# SCH_Better_Heating_Plate_2022-11-13.net
KiCad netlist of a schematic drawn in EasyEDA
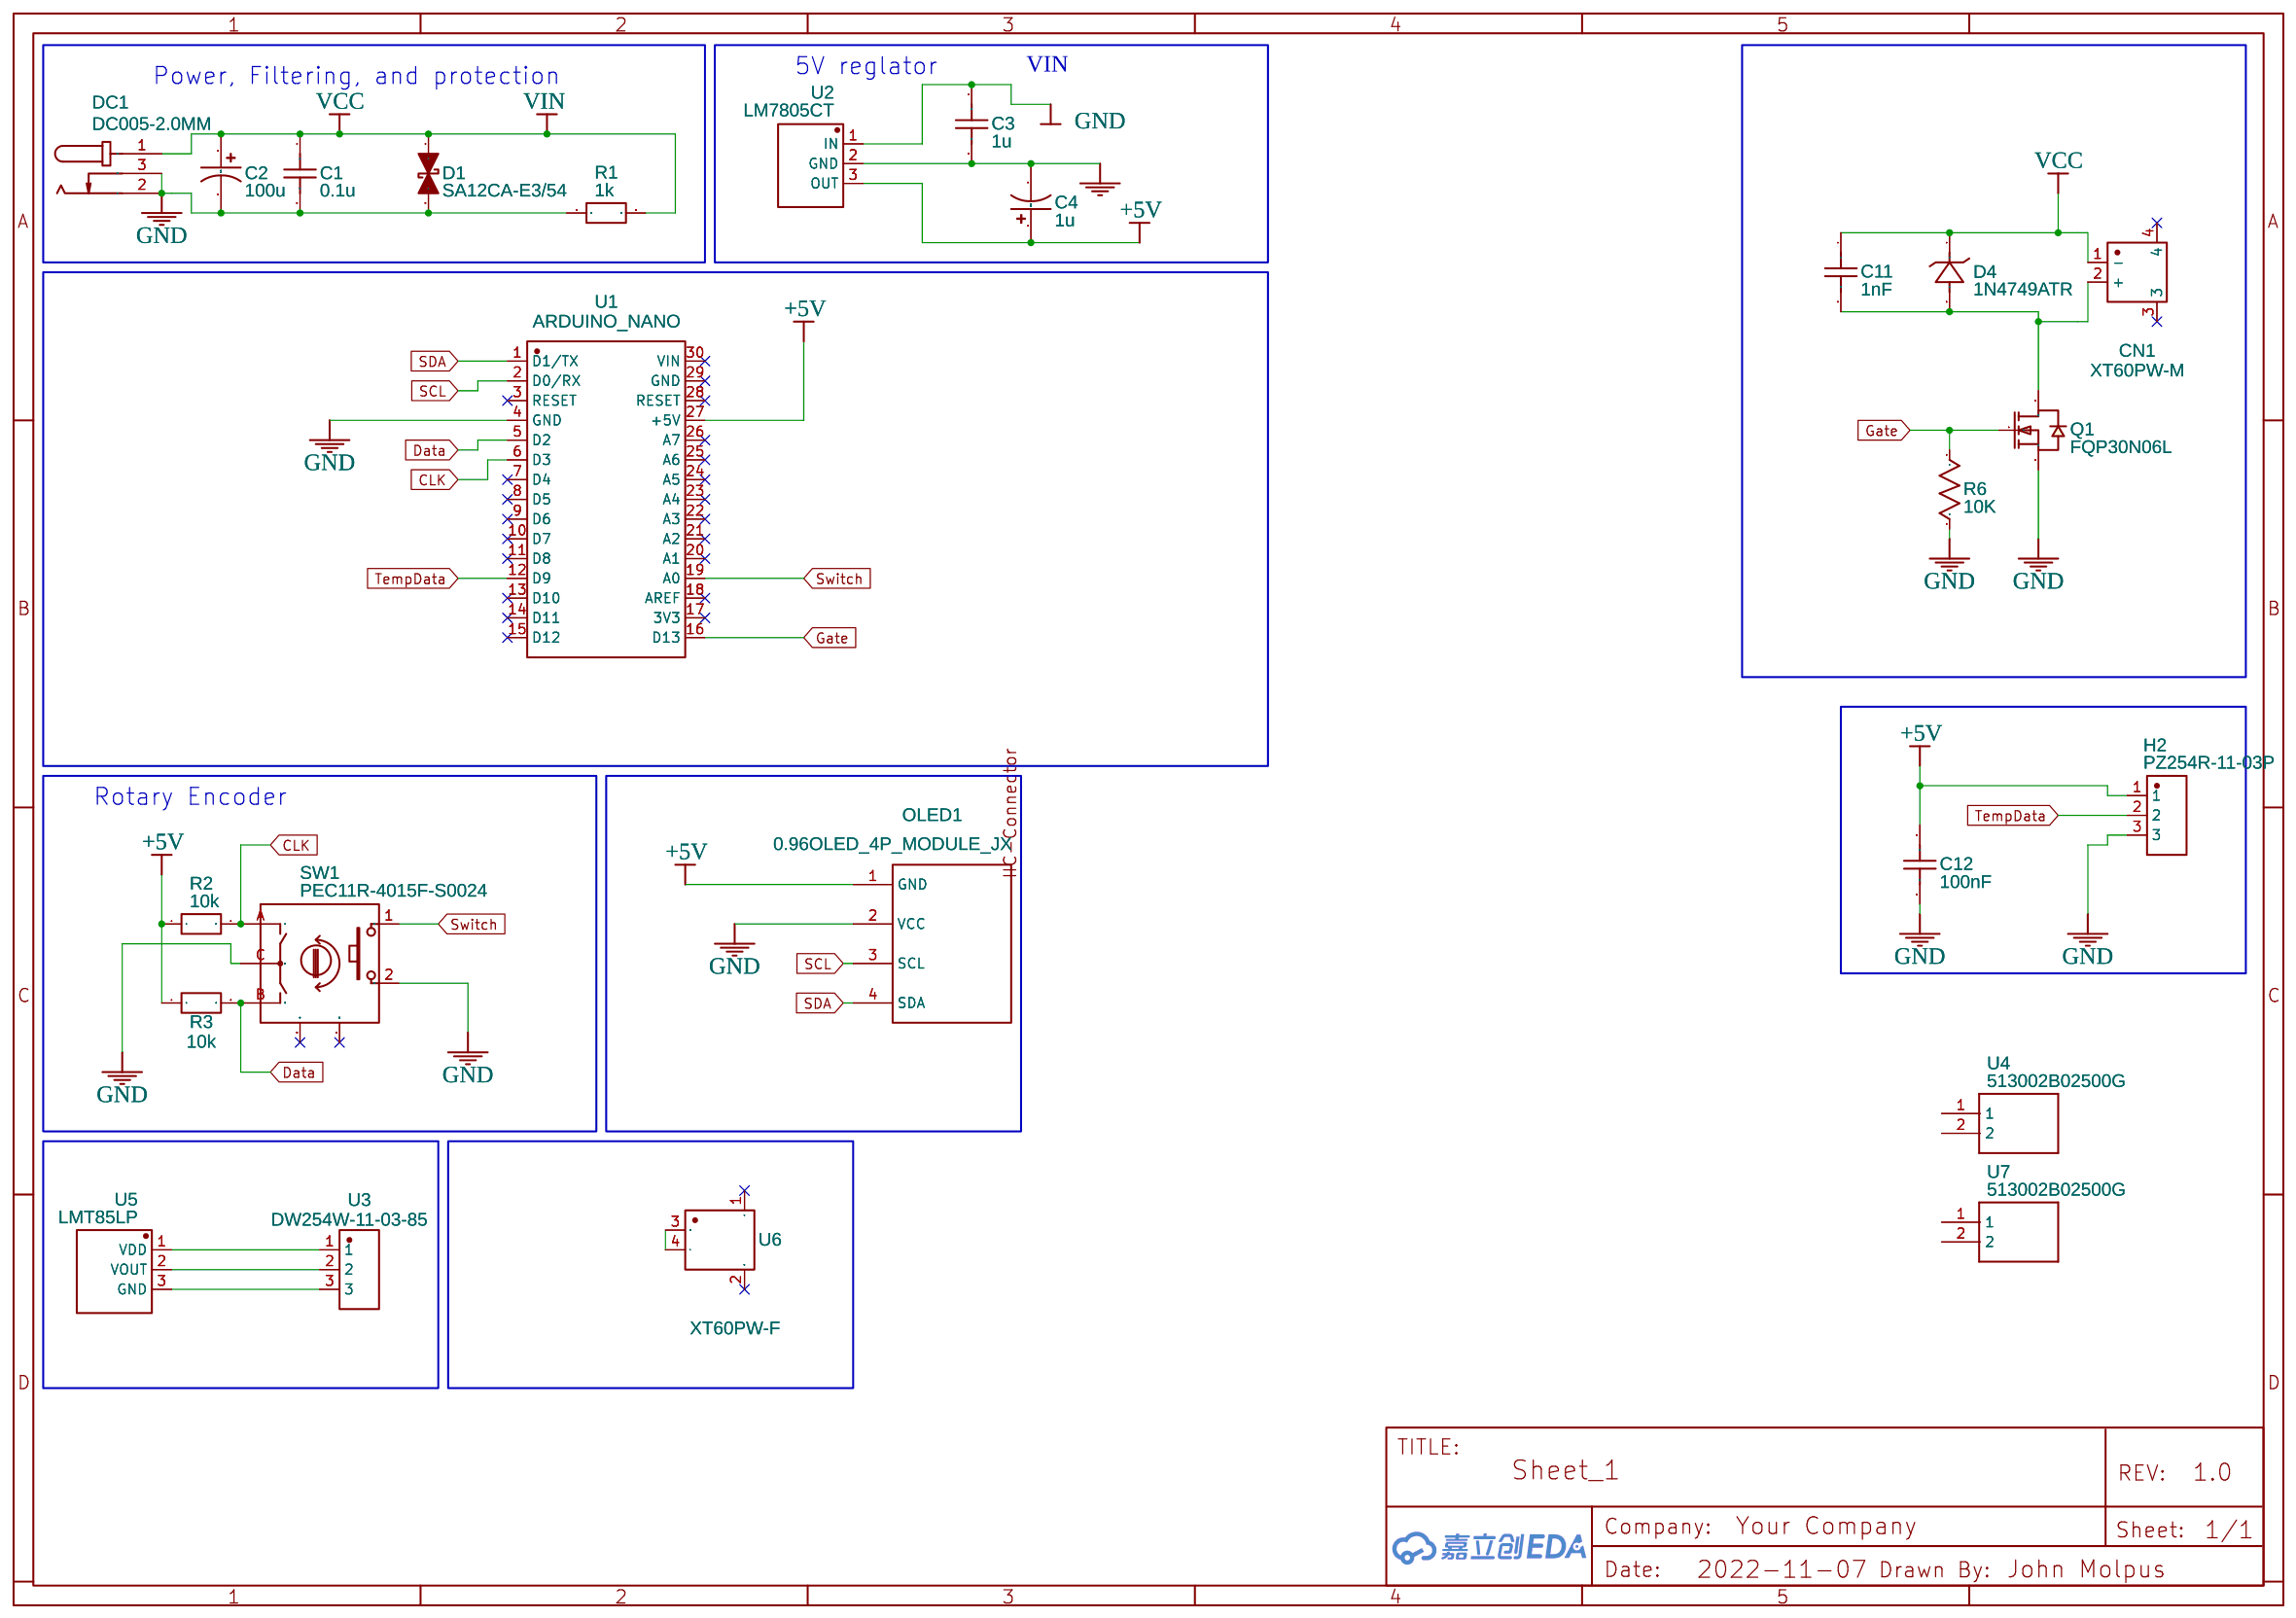
[diagram p0: schematic sheet]

(export (version "E")
  (design (tool "Eeschema 10.0.6"))
  (components
    (comp (ref "C1") (value "0.1u") (libsource (lib "") (part "C_RAD-0.2_US")))
    (comp (ref "C2") (value "100u") (libsource (lib "") (part "CE_TH_D3.0×F1.5_US_1")))
    (comp (ref "C3") (value "1u") (libsource (lib "") (part "C_RAD-0.1_US")))
    (comp (ref "C4") (value "1u") (libsource (lib "") (part "CE_TH_D3.0×F1.5_US")))
    (comp (ref "C11") (value "1nF") (libsource (lib "") (part "C_RAD-0.1_US")))
    (comp (ref "C12") (value "100nF") (libsource (lib "") (part "C_RAD-0.1_US")))
    (comp (ref "CN1")
      (value "XT60PW-M")
      (fields (field (name "BOM_Supplier Part") "C98732"))
      (libsource (lib "") (part "XT60PW-M"))
    )
    (comp (ref "D1")
      (value "SA12CA-E3/54")
      (fields (field (name "BOM_Supplier Part") "C1975517"))
      (libsource (lib "") (part "SA12CA-E3/54"))
    )
    (comp (ref "D4")
      (value "1N4749ATR")
      (fields (field (name "BOM_Supplier Part") "C890088"))
      (libsource (lib "") (part "1N4749ATR"))
    )
    (comp (ref "DC1")
      (value "DC005-2.0MM")
      (fields (field (name "BOM_Supplier Part") "C111567"))
      (libsource (lib "") (part "DC005-2.0MM"))
    )
    (comp (ref "H2")
      (value "PZ254R-11-03P")
      (fields (field (name "BOM_Supplier Part") "C492411"))
      (libsource (lib "") (part "PZ254R-11-03P"))
    )
    (comp (ref "OLED1")
      (value "0.96OLED_4P_MODULE_JX")
      (fields (field (name "BOM_Supplier Part") "C9900004566"))
      (libsource (lib "") (part "0.96OLED_4P_MODULE_JX"))
    )
    (comp (ref "Q1")
      (value "FQP30N06L")
      (fields
        (field (name "BOM_Manufacturer Part") "FQP30N06L-VB")
        (field (name "BOM_Supplier Part") "C878826")
      )
      (libsource (lib "") (part "FQP30N06L"))
    )
    (comp (ref "R1") (value "1k") (libsource (lib "") (part "R_AXIAL-0.3_EU")))
    (comp (ref "R2") (value "10k") (libsource (lib "") (part "R_AXIAL-0.3_EU")))
    (comp (ref "R3") (value "10k") (libsource (lib "") (part "R_AXIAL-0.3_EU")))
    (comp (ref "R6") (value "10K") (libsource (lib "") (part "R_AXIAL-0.3_US")))
    (comp (ref "SW1")
      (value "PEC11R-4015F-S0024")
      (fields (field (name "BOM_Supplier Part") "C143789"))
      (libsource (lib "") (part "PEC11R-4015F-S0024"))
    )
    (comp (ref "U1")
      (value "ARDUINO_NANO")
      (fields (field (name "BOM_Supplier Part") "C9900017879"))
      (libsource (lib "") (part "ARDUINO_NANO"))
    )
    (comp (ref "U2")
      (value "LM7805CT")
      (fields (field (name "BOM_Supplier Part") "C22146"))
      (libsource (lib "") (part "LM7805CT"))
    )
    (comp (ref "U3")
      (value "DW254W-11-03-85")
      (fields (field (name "BOM_Supplier Part") "C2935993"))
      (libsource (lib "") (part "DW254W-11-03-85"))
    )
    (comp (ref "U4") (value "513002B02500G") (libsource (lib "") (part "513002B02500G")))
    (comp (ref "U5")
      (value "LMT85LP")
      (fields (field (name "BOM_Supplier Part") "C75856"))
      (libsource (lib "") (part "LMT85LP"))
    )
    (comp (ref "U6")
      (value "XT60PW-F")
      (fields
        (field (name "BOM_Manufacturer Part") "XT60PW-F 母头 板插卧式")
        (field (name "BOM_Supplier Part") "C9900000737")
      )
      (libsource (lib "") (part "XT60PW-F"))
    )
    (comp (ref "U7") (value "513002B02500G") (libsource (lib "") (part "513002B02500G")))
  )
  (nets
    (net (code "1") (name "+5V") (class "Default")
      (node (ref "C12") (pin "1") (pinfunction "1_1") (pintype "unspecified"))
      (node (ref "C4") (pin "1") (pinfunction "1_1") (pintype "unspecified"))
      (node (ref "H2") (pin "1") (pinfunction "1_1") (pintype "unspecified"))
      (node (ref "OLED1") (pin "1") (pinfunction "GND_1") (pintype "unspecified"))
      (node (ref "R2") (pin "1") (pinfunction "1_1") (pintype "unspecified"))
      (node (ref "R3") (pin "1") (pinfunction "1_1") (pintype "unspecified"))
      (node (ref "U1") (pin "27") (pinfunction "+5V_27") (pintype "unspecified"))
      (node (ref "U2") (pin "3") (pinfunction "OUT_3") (pintype "unspecified"))
    )
    (net (code "2") (name "CLK") (class "Default")
      (node (ref "R2") (pin "2") (pinfunction "2_2") (pintype "unspecified"))
      (node (ref "SW1") (pin "A") (pinfunction "A_A") (pintype "unspecified"))
      (node (ref "U1") (pin "6") (pinfunction "D3_6") (pintype "unspecified"))
    )
    (net (code "3") (name "Data") (class "Default")
      (node (ref "R3") (pin "2") (pinfunction "2_2") (pintype "unspecified"))
      (node (ref "SW1") (pin "B") (pinfunction "B_B") (pintype "unspecified"))
      (node (ref "U1") (pin "5") (pinfunction "D2_5") (pintype "unspecified"))
    )
    (net (code "4") (name "GND") (class "Default")
      (node (ref "C1") (pin "2") (pinfunction "2_2") (pintype "unspecified"))
      (node (ref "C12") (pin "2") (pinfunction "2_2") (pintype "unspecified"))
      (node (ref "C2") (pin "2") (pinfunction "2_2") (pintype "unspecified"))
      (node (ref "C3") (pin "2") (pinfunction "2_2") (pintype "unspecified"))
      (node (ref "C4") (pin "2") (pinfunction "2_2") (pintype "unspecified"))
      (node (ref "D1") (pin "2") (pinfunction "A_2") (pintype "input"))
      (node (ref "DC1") (pin "2") (pinfunction "2_2") (pintype "unspecified"))
      (node (ref "DC1") (pin "3") (pinfunction "3_3") (pintype "unspecified"))
      (node (ref "H2") (pin "3") (pinfunction "3_3") (pintype "unspecified"))
      (node (ref "OLED1") (pin "2") (pinfunction "VCC_2") (pintype "unspecified"))
      (node (ref "Q1") (pin "3") (pinfunction "S_3") (pintype "unspecified"))
      (node (ref "R1") (pin "1") (pinfunction "1_1") (pintype "unspecified"))
      (node (ref "R6") (pin "2") (pinfunction "2_2") (pintype "unspecified"))
      (node (ref "SW1") (pin "2") (pinfunction "2_2") (pintype "unspecified"))
      (node (ref "SW1") (pin "C") (pinfunction "C_C") (pintype "unspecified"))
      (node (ref "U1") (pin "4") (pinfunction "GND_4") (pintype "unspecified"))
      (node (ref "U2") (pin "2") (pinfunction "GND_2") (pintype "unspecified"))
    )
    (net (code "5") (name "Gate") (class "Default")
      (node (ref "Q1") (pin "1") (pinfunction "G_1") (pintype "unspecified"))
      (node (ref "R6") (pin "1") (pinfunction "1_1") (pintype "unspecified"))
      (node (ref "U1") (pin "16") (pinfunction "D13_16") (pintype "unspecified"))
    )
    (net (code "6") (name "Net-(CN1-+)") (class "Default")
      (node (ref "C11") (pin "2") (pinfunction "2_2") (pintype "unspecified"))
      (node (ref "CN1") (pin "2") (pinfunction "+_2") (pintype "unspecified"))
      (node (ref "D4") (pin "2") (pinfunction "A_2") (pintype "unspecified"))
      (node (ref "Q1") (pin "2") (pinfunction "D_2") (pintype "unspecified"))
    )
    (net (code "7") (name "Net-(U5-GND)") (class "Default")
      (node (ref "U3") (pin "3") (pinfunction "3_3") (pintype "unspecified"))
      (node (ref "U5") (pin "3") (pinfunction "GND_3") (pintype "unspecified"))
    )
    (net (code "8") (name "Net-(U5-VDD)") (class "Default")
      (node (ref "U3") (pin "1") (pinfunction "1_1") (pintype "unspecified"))
      (node (ref "U5") (pin "1") (pinfunction "VDD_1") (pintype "unspecified"))
    )
    (net (code "9") (name "Net-(U5-VOUT)") (class "Default")
      (node (ref "U3") (pin "2") (pinfunction "2_2") (pintype "unspecified"))
      (node (ref "U5") (pin "2") (pinfunction "VOUT_2") (pintype "unspecified"))
    )
    (net (code "10") (name "Net-(U6-Pad3)") (class "Default")
      (node (ref "U6") (pin "3") (pinfunction "3_3") (pintype "unspecified"))
      (node (ref "U6") (pin "4") (pinfunction "4_4") (pintype "unspecified"))
    )
    (net (code "11") (name "SCL") (class "Default")
      (node (ref "OLED1") (pin "3") (pinfunction "SCL_3") (pintype "unspecified"))
      (node (ref "U1") (pin "2") (pinfunction "D0/RX_2") (pintype "unspecified"))
    )
    (net (code "12") (name "SDA") (class "Default")
      (node (ref "OLED1") (pin "4") (pinfunction "SDA_4") (pintype "unspecified"))
      (node (ref "U1") (pin "1") (pinfunction "D1/TX_1") (pintype "unspecified"))
    )
    (net (code "13") (name "Switch") (class "Default")
      (node (ref "SW1") (pin "1") (pinfunction "1_1") (pintype "unspecified"))
      (node (ref "U1") (pin "19") (pinfunction "A0_19") (pintype "unspecified"))
    )
    (net (code "14") (name "TempData") (class "Default")
      (node (ref "H2") (pin "2") (pinfunction "2_2") (pintype "unspecified"))
      (node (ref "U1") (pin "12") (pinfunction "D9_12") (pintype "unspecified"))
    )
    (net (code "15") (name "VCC") (class "Default")
      (node (ref "C1") (pin "1") (pinfunction "1_1") (pintype "unspecified"))
      (node (ref "C11") (pin "1") (pinfunction "1_1") (pintype "unspecified"))
      (node (ref "C2") (pin "1") (pinfunction "1_1") (pintype "unspecified"))
      (node (ref "C3") (pin "1") (pinfunction "1_1") (pintype "unspecified"))
      (node (ref "CN1") (pin "1") (pinfunction "-_1") (pintype "unspecified"))
      (node (ref "D1") (pin "1") (pinfunction "K_1") (pintype "input"))
      (node (ref "D4") (pin "1") (pinfunction "C_1") (pintype "unspecified"))
      (node (ref "DC1") (pin "1") (pinfunction "1_1") (pintype "unspecified"))
      (node (ref "R1") (pin "2") (pinfunction "2_2") (pintype "unspecified"))
      (node (ref "U2") (pin "1") (pinfunction "IN_1") (pintype "unspecified"))
    )
    (net (code "16") (name "unconnected-(CN1-Pad3)") (class "Default")
      (node (ref "CN1") (pin "3") (pinfunction "3_3") (pintype "unspecified+no_connect"))
    )
    (net (code "17") (name "unconnected-(CN1-Pad4)") (class "Default")
      (node (ref "CN1") (pin "4") (pinfunction "4_4") (pintype "unspecified+no_connect"))
    )
    (net (code "18") (name "unconnected-(SW1-PadMT1)") (class "Default")
      (node (ref "SW1") (pin "MT1") (pinfunction "MT1_MT1") (pintype "unspecified+no_connect"))
    )
    (net (code "19") (name "unconnected-(SW1-PadMT2)") (class "Default")
      (node (ref "SW1") (pin "MT2") (pinfunction "MT2_MT2") (pintype "unspecified+no_connect"))
    )
    (net (code "20") (name "unconnected-(U1-3V3-Pad17)") (class "Default")
      (node (ref "U1") (pin "17") (pinfunction "3V3_17") (pintype "unspecified+no_connect"))
    )
    (net (code "21") (name "unconnected-(U1-A1-Pad20)") (class "Default")
      (node (ref "U1") (pin "20") (pinfunction "A1_20") (pintype "unspecified+no_connect"))
    )
    (net (code "22") (name "unconnected-(U1-A2-Pad21)") (class "Default")
      (node (ref "U1") (pin "21") (pinfunction "A2_21") (pintype "unspecified+no_connect"))
    )
    (net (code "23") (name "unconnected-(U1-A3-Pad22)") (class "Default")
      (node (ref "U1") (pin "22") (pinfunction "A3_22") (pintype "unspecified+no_connect"))
    )
    (net (code "24") (name "unconnected-(U1-A4-Pad23)") (class "Default")
      (node (ref "U1") (pin "23") (pinfunction "A4_23") (pintype "unspecified+no_connect"))
    )
    (net (code "25") (name "unconnected-(U1-A5-Pad24)") (class "Default")
      (node (ref "U1") (pin "24") (pinfunction "A5_24") (pintype "unspecified+no_connect"))
    )
    (net (code "26") (name "unconnected-(U1-A6-Pad25)") (class "Default")
      (node (ref "U1") (pin "25") (pinfunction "A6_25") (pintype "unspecified+no_connect"))
    )
    (net (code "27") (name "unconnected-(U1-A7-Pad26)") (class "Default")
      (node (ref "U1") (pin "26") (pinfunction "A7_26") (pintype "unspecified+no_connect"))
    )
    (net (code "28") (name "unconnected-(U1-AREF-Pad18)") (class "Default")
      (node (ref "U1") (pin "18") (pinfunction "AREF_18") (pintype "unspecified+no_connect"))
    )
    (net (code "29") (name "unconnected-(U1-D4-Pad7)") (class "Default")
      (node (ref "U1") (pin "7") (pinfunction "D4_7") (pintype "unspecified+no_connect"))
    )
    (net (code "30") (name "unconnected-(U1-D5-Pad8)") (class "Default")
      (node (ref "U1") (pin "8") (pinfunction "D5_8") (pintype "unspecified+no_connect"))
    )
    (net (code "31") (name "unconnected-(U1-D6-Pad9)") (class "Default")
      (node (ref "U1") (pin "9") (pinfunction "D6_9") (pintype "unspecified+no_connect"))
    )
    (net (code "32") (name "unconnected-(U1-D7-Pad10)") (class "Default")
      (node (ref "U1") (pin "10") (pinfunction "D7_10") (pintype "unspecified+no_connect"))
    )
    (net (code "33") (name "unconnected-(U1-D8-Pad11)") (class "Default")
      (node (ref "U1") (pin "11") (pinfunction "D8_11") (pintype "unspecified+no_connect"))
    )
    (net (code "34") (name "unconnected-(U1-D10-Pad13)") (class "Default")
      (node (ref "U1") (pin "13") (pinfunction "D10_13") (pintype "unspecified+no_connect"))
    )
    (net (code "35") (name "unconnected-(U1-D11-Pad14)") (class "Default")
      (node (ref "U1") (pin "14") (pinfunction "D11_14") (pintype "unspecified+no_connect"))
    )
    (net (code "36") (name "unconnected-(U1-D12-Pad15)") (class "Default")
      (node (ref "U1") (pin "15") (pinfunction "D12_15") (pintype "unspecified+no_connect"))
    )
    (net (code "37") (name "unconnected-(U1-GND-Pad29)") (class "Default")
      (node (ref "U1") (pin "29") (pinfunction "GND_29") (pintype "unspecified+no_connect"))
    )
    (net (code "38") (name "unconnected-(U1-RESET-Pad3)") (class "Default")
      (node (ref "U1") (pin "3") (pinfunction "RESET_3") (pintype "unspecified+no_connect"))
    )
    (net (code "39") (name "unconnected-(U1-RESET-Pad28)") (class "Default")
      (node (ref "U1") (pin "28") (pinfunction "RESET_28") (pintype "unspecified+no_connect"))
    )
    (net (code "40") (name "unconnected-(U1-VIN-Pad30)") (class "Default")
      (node (ref "U1") (pin "30") (pinfunction "VIN_30") (pintype "unspecified+no_connect"))
    )
    (net (code "41") (name "unconnected-(U4-Pad1)") (class "Default")
      (node (ref "U4") (pin "1") (pinfunction "1_1") (pintype "bidirectional"))
    )
    (net (code "42") (name "unconnected-(U4-Pad2)") (class "Default")
      (node (ref "U4") (pin "2") (pinfunction "2_2") (pintype "bidirectional"))
    )
    (net (code "43") (name "unconnected-(U6-Pad1)") (class "Default")
      (node (ref "U6") (pin "1") (pinfunction "1_1") (pintype "unspecified+no_connect"))
    )
    (net (code "44") (name "unconnected-(U6-Pad2)") (class "Default")
      (node (ref "U6") (pin "2") (pinfunction "2_2") (pintype "unspecified+no_connect"))
    )
    (net (code "45") (name "unconnected-(U7-Pad1)") (class "Default")
      (node (ref "U7") (pin "1") (pinfunction "1_1") (pintype "bidirectional"))
    )
    (net (code "46") (name "unconnected-(U7-Pad2)") (class "Default")
      (node (ref "U7") (pin "2") (pinfunction "2_2") (pintype "bidirectional"))
    )
  )
)
